# 2_Power.net
KiCad netlist of a schematic drawn in Altium Designer
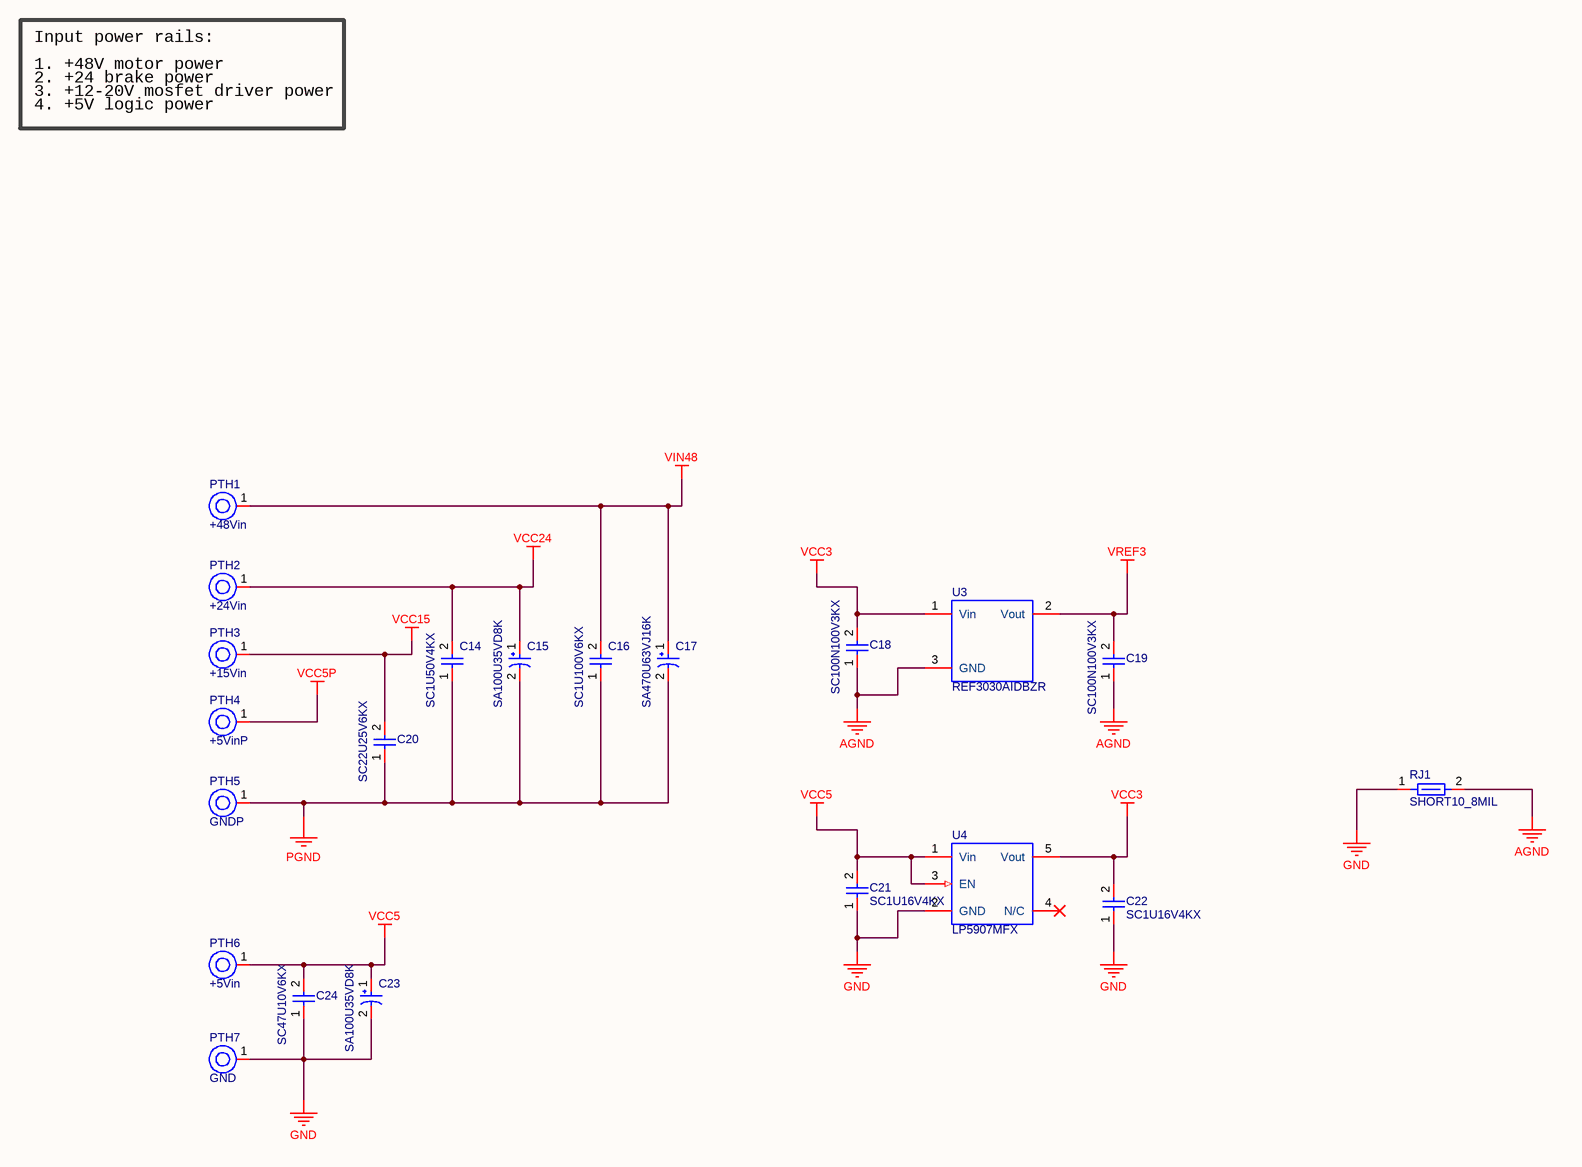
[diagram p0: 2_Power.SchDoc]

(export (version "E")
  (design (tool "Eeschema 10.0.6"))
  (components
    (comp (ref "C14")
      (value "SC1U50V4KX")
      (footprint "CAPC0805(2012)145_L")
      (description "CAP 1uF 50V ±10% 0805(1610 Metric) Thickness 1.2mm SMD")
      (libsource (lib "PUMAlib") (part "CAP(0805)1UF50V"))
    )
    (comp (ref "C15")
      (value "SA100U35VD8K")
      (footprint "CAPAE(D8)7666X80L")
      (description "CAP 100uF 35V ±10% D8 Thickness 7.7mm SMD")
      (libsource (lib "PUMAlib") (part "CAP(D8)100UF35V"))
    )
    (comp (ref "C16")
      (value "SC1U100V6KX")
      (footprint "CAPC1206(3216)")
      (description "CAP 1uF 100V ±10% 1206(3216 Metric) Thickness 1.8mm SMD")
      (libsource (lib "PUMAlib") (part "CAP(1206)1UF100V"))
    )
    (comp (ref "C17")
      (value "SA470U63VJ16K")
      (footprint "CAPAE184170X170L")
      (description "EEVFK1J471M CAP 470uF 63V ±10% J16 Thickness 17mm SMD")
      (libsource (lib "PUMAlib") (part "CAP(J16)470UF63V"))
    )
    (comp (ref "C18")
      (value "SC100N100V3KX")
      (footprint "CAPC0603(1608)100_L")
      (description "CAP 100nF 100V ±10% 0603(1608 Metric) Thickness 1mm SMD")
      (libsource (lib "PUMAlib") (part "CAP(0603)100nF100V"))
    )
    (comp (ref "C19")
      (value "SC100N100V3KX")
      (footprint "CAPC0603(1608)100_L")
      (description "CAP 100nF 100V ±10% 0603(1608 Metric) Thickness 1mm SMD")
      (libsource (lib "PUMAlib") (part "CAP(0603)100nF100V"))
    )
    (comp (ref "C20")
      (value "SC22U25V6KX")
      (footprint "CAPC1206(3216)")
      (description "CAP 22uF 25V ±10% 1206(3216 Metric) Thickness 1.8mm SMD")
      (libsource (lib "PUMAlib") (part "CAP(1206)22UF25V"))
    )
    (comp (ref "C21")
      (value "SC1U16V4KX")
      (footprint "CAPC0805(2012)145_L")
      (description "CAP 1uF 16V ±10% 0805(1610 Metric) Thickness 0.6mm SMD")
      (libsource (lib "Schlib") (part "CAP(0805)1UF16V"))
    )
    (comp (ref "C22")
      (value "SC1U16V4KX")
      (footprint "CAPC0805(2012)145_L")
      (description "CAP 1uF 16V ±10% 0805(1610 Metric) Thickness 0.6mm SMD")
      (libsource (lib "Schlib") (part "CAP(0805)1UF16V"))
    )
    (comp (ref "C23")
      (value "SA100U35VD8K")
      (footprint "CAPAE(D8)7666X80L")
      (description "CAP 100uF 35V ±10% D8 Thickness 7.7mm SMD")
      (libsource (lib "PUMAlib") (part "CAP(D8)100UF35V"))
    )
    (comp (ref "C24")
      (value "SC47U10V6KX")
      (footprint "CAPC1206(3216)")
      (description "CAP 47uF 10V ±10% 1206(3216 Metric) Thickness 1.6mm SMD")
      (libsource (lib "PUMAlib") (part "CAP(1206)47UF10V"))
    )
    (comp (ref "PTH1")
      (value "+48Vin")
      (footprint "POWERHOLE")
      (description "2mm hole 3.5mm pad")
      (libsource (lib "PUMAlib") (part "PTH-2M"))
    )
    (comp (ref "PTH2")
      (value "+24Vin")
      (footprint "POWERHOLE")
      (description "2mm hole 3.5mm pad")
      (libsource (lib "PUMAlib") (part "PTH-2M"))
    )
    (comp (ref "PTH3")
      (value "+15Vin")
      (footprint "POWERHOLE-LP")
      (description "1.2mm hole 2mm pad")
      (libsource (lib "PUMAlib") (part "PTH-1D2M"))
    )
    (comp (ref "PTH4")
      (value "+5VinP")
      (footprint "POWERHOLE-LP")
      (description "1.2mm hole 2mm pad")
      (libsource (lib "PUMAlib") (part "PTH-1D2M"))
    )
    (comp (ref "PTH5")
      (value "GNDP")
      (footprint "POWERHOLE")
      (description "2mm hole 3.5mm pad")
      (libsource (lib "PUMAlib") (part "PTH-2M"))
    )
    (comp (ref "PTH6")
      (value "+5Vin")
      (footprint "POWERHOLE-LP")
      (description "1.2mm hole 2mm pad")
      (libsource (lib "PUMAlib") (part "PTH-1D2M"))
    )
    (comp (ref "PTH7")
      (value "GND")
      (footprint "POWERHOLE-LP")
      (description "1.2mm hole 2mm pad")
      (libsource (lib "PUMAlib") (part "PTH-1D2M"))
    )
    (comp (ref "RJ1")
      (value "SHORT10_8MIL")
      (footprint "SHORT10_8MIL-FP")
      (description "Net tie (10x8mil)")
      (fields (field (name "TOLERANCE") "5%"))
      (libsource (lib "PUMAlib") (part "SHORT*"))
    )
    (comp (ref "U3")
      (value "REF3030AIDBZR")
      (footprint "SOT95P237X112-3L")
      (description "3V 25mA 0.2%")
      (libsource (lib "PUMAlib") (part "REF-REF3030"))
    )
    (comp (ref "U4")
      (value "LP5907MFX")
      (footprint "SOT95P280X145-5L")
      (description "3.3V 250mA")
      (libsource (lib "Schlib") (part "LP5907V3.3"))
    )
  )
  (nets
    (net (code "1") (name "AGND") (class "Default")
      (node (ref "C18") (pin "1") (pinfunction "1_1") (pintype "passive"))
      (node (ref "C19") (pin "1") (pinfunction "1_1") (pintype "passive"))
      (node (ref "RJ1") (pin "2") (pinfunction "2_2") (pintype "passive"))
      (node (ref "U3") (pin "3") (pinfunction "GND_3") (pintype "power_in"))
    )
    (net (code "2") (name "GND") (class "Default")
      (node (ref "C21") (pin "1") (pinfunction "1_1") (pintype "passive"))
      (node (ref "C22") (pin "1") (pinfunction "1_1") (pintype "passive"))
      (node (ref "C23") (pin "2") (pinfunction "2_2") (pintype "passive"))
      (node (ref "C24") (pin "1") (pinfunction "1_1") (pintype "passive"))
      (node (ref "PTH7") (pin "1") (pinfunction "H1_1") (pintype "passive"))
      (node (ref "RJ1") (pin "1") (pinfunction "1_1") (pintype "passive"))
      (node (ref "U4") (pin "2") (pinfunction "GND_2") (pintype "power_in"))
    )
    (net (code "3") (name "PGND") (class "Default")
      (node (ref "C14") (pin "1") (pinfunction "1_1") (pintype "passive"))
      (node (ref "C15") (pin "2") (pinfunction "2_2") (pintype "passive"))
      (node (ref "C16") (pin "1") (pinfunction "1_1") (pintype "passive"))
      (node (ref "C17") (pin "2") (pinfunction "2_2") (pintype "passive"))
      (node (ref "C20") (pin "1") (pinfunction "1_1") (pintype "passive"))
      (node (ref "PTH5") (pin "1") (pinfunction "H1_1") (pintype "passive"))
    )
    (net (code "4") (name "VCC3") (class "Default")
      (node (ref "C18") (pin "2") (pinfunction "2_2") (pintype "passive"))
      (node (ref "C22") (pin "2") (pinfunction "2_2") (pintype "passive"))
      (node (ref "U3") (pin "1") (pinfunction "Vin_1") (pintype "power_in"))
      (node (ref "U4") (pin "5") (pinfunction "Vout_5") (pintype "power_in"))
    )
    (net (code "5") (name "VCC5") (class "Default")
      (node (ref "C21") (pin "2") (pinfunction "2_2") (pintype "passive"))
      (node (ref "C23") (pin "1") (pinfunction "1_1") (pintype "passive"))
      (node (ref "C24") (pin "2") (pinfunction "2_2") (pintype "passive"))
      (node (ref "PTH6") (pin "1") (pinfunction "H1_1") (pintype "passive"))
      (node (ref "U4") (pin "1") (pinfunction "Vin_1") (pintype "power_in"))
      (node (ref "U4") (pin "3") (pinfunction "EN_3") (pintype "input"))
    )
    (net (code "6") (name "VCC5P") (class "Default")
      (node (ref "PTH4") (pin "1") (pinfunction "H1_1") (pintype "passive"))
    )
    (net (code "7") (name "VCC15") (class "Default")
      (node (ref "C20") (pin "2") (pinfunction "2_2") (pintype "passive"))
      (node (ref "PTH3") (pin "1") (pinfunction "H1_1") (pintype "passive"))
    )
    (net (code "8") (name "VCC24") (class "Default")
      (node (ref "C14") (pin "2") (pinfunction "2_2") (pintype "passive"))
      (node (ref "C15") (pin "1") (pinfunction "1_1") (pintype "passive"))
      (node (ref "PTH2") (pin "1") (pinfunction "H1_1") (pintype "passive"))
    )
    (net (code "9") (name "VIN48") (class "Default")
      (node (ref "C16") (pin "2") (pinfunction "2_2") (pintype "passive"))
      (node (ref "C17") (pin "1") (pinfunction "1_1") (pintype "passive"))
      (node (ref "PTH1") (pin "1") (pinfunction "H1_1") (pintype "passive"))
    )
    (net (code "10") (name "VREF3") (class "Default")
      (node (ref "C19") (pin "2") (pinfunction "2_2") (pintype "passive"))
      (node (ref "U3") (pin "2") (pinfunction "Vout_2") (pintype "power_in"))
    )
    (net (code "11") (name "unconnected-(U4-N{slash}C-Pad4)") (class "Default")
      (node (ref "U4") (pin "4") (pinfunction "N/C_4") (pintype "passive+no_connect"))
    )
  )
)
